# hemera_charger_A.net
KiCad netlist of a schematic drawn in EAGLE
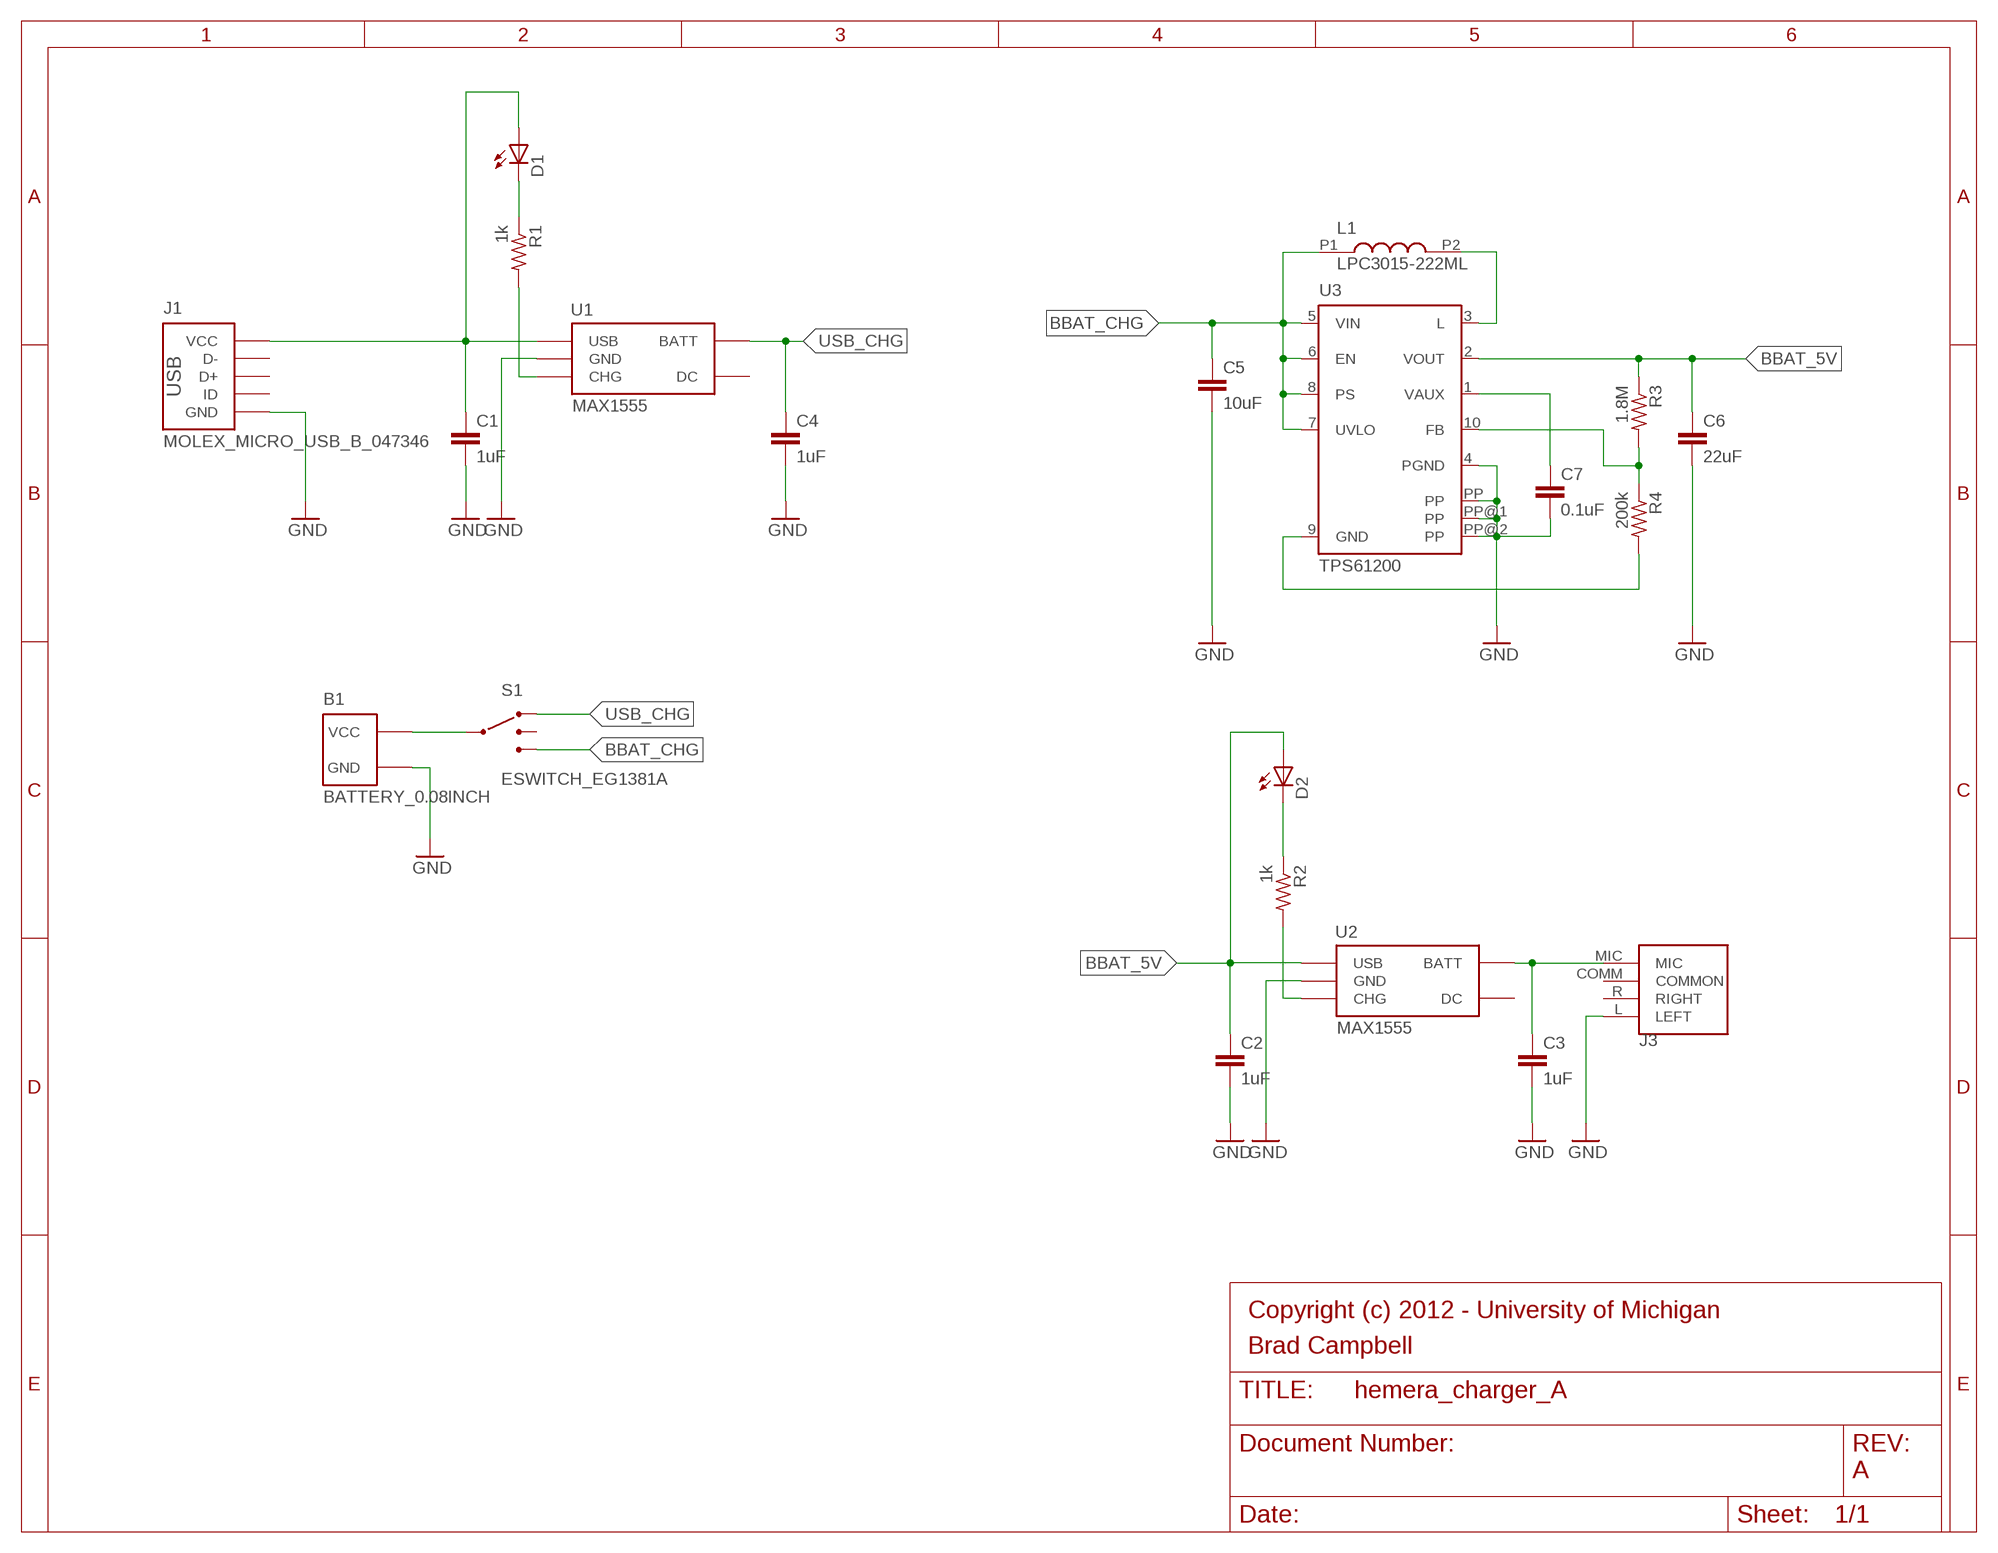
[diagram p0: schematic, sheet 1]

(export (version "E")
  (design (tool "Eeschema 10.0.6"))
  (components
    (comp (ref "B1")
      (value "BATTERY_0.08INCH")
      (footprint "eagle-import:BATTERY_0.08INCH")
      (libsource (lib "eagle-import") (part "BATTERY_0.08INCH"))
    )
    (comp (ref "C1")
      (value "1uF")
      (footprint "eagle-import:C0603")
      (libsource (lib "eagle-import") (part "C-EUC0603"))
    )
    (comp (ref "C2")
      (value "1uF")
      (footprint "eagle-import:C0603")
      (libsource (lib "eagle-import") (part "C-EUC0603"))
    )
    (comp (ref "C3")
      (value "1uF")
      (footprint "eagle-import:C0603")
      (libsource (lib "eagle-import") (part "C-EUC0603"))
    )
    (comp (ref "C4")
      (value "1uF")
      (footprint "eagle-import:C0603")
      (libsource (lib "eagle-import") (part "C-EUC0603"))
    )
    (comp (ref "C5")
      (value "10uF")
      (footprint "eagle-import:C0603")
      (libsource (lib "eagle-import") (part "C-EUC0603"))
    )
    (comp (ref "C6")
      (value "22uF")
      (footprint "eagle-import:C0603")
      (libsource (lib "eagle-import") (part "C-EUC0603"))
    )
    (comp (ref "C7")
      (value "0.1uF")
      (footprint "eagle-import:C0603")
      (libsource (lib "eagle-import") (part "C-EUC0603"))
    )
    (comp (ref "D1")
      (value "LED0603")
      (footprint "eagle-import:LED-0603")
      (libsource (lib "eagle-import") (part "LED0603"))
    )
    (comp (ref "D2")
      (value "LED0603")
      (footprint "eagle-import:LED-0603")
      (libsource (lib "eagle-import") (part "LED0603"))
    )
    (comp (ref "J1")
      (value "MOLEX_MICRO_USB_B_047346")
      (footprint "eagle-import:MOLEX_MICRO_USB_B_047346")
      (libsource (lib "eagle-import") (part "MOLEX_MICRO_USB_B_047346"))
    )
    (comp (ref "J3")
      (value "3.5JACK4CONNSUNSTONE_QUICKTURN")
      (footprint "eagle-import:PLUGBOARDCONNECTOR_SUNSTONE")
      (libsource (lib "eagle-import") (part "3.5JACK4CONNSUNSTONE_QUICKTURN"))
    )
    (comp (ref "L1")
      (value "LPC3015-222ML")
      (footprint "eagle-import:LPS3015")
      (libsource (lib "eagle-import") (part "LPC3015"))
    )
    (comp (ref "R1")
      (value "1k")
      (footprint "eagle-import:R0603")
      (libsource (lib "eagle-import") (part "R-US_R0603"))
    )
    (comp (ref "R2")
      (value "1k")
      (footprint "eagle-import:R0603")
      (libsource (lib "eagle-import") (part "R-US_R0603"))
    )
    (comp (ref "R3")
      (value "1.8M")
      (footprint "eagle-import:R0603")
      (libsource (lib "eagle-import") (part "R-US_R0603"))
    )
    (comp (ref "R4")
      (value "200k")
      (footprint "eagle-import:R0603")
      (libsource (lib "eagle-import") (part "R-US_R0603"))
    )
    (comp (ref "S1")
      (value "ESWITCH_EG1381A")
      (footprint "eagle-import:ESWITCH_EG1381")
      (libsource (lib "eagle-import") (part "ESWITCH_EG1381A"))
    )
    (comp (ref "U1")
      (value "MAX1555")
      (footprint "eagle-import:SOT23-5")
      (libsource (lib "eagle-import") (part "MAX1555"))
    )
    (comp (ref "U2")
      (value "MAX1555")
      (footprint "eagle-import:SOT23-5")
      (libsource (lib "eagle-import") (part "MAX1555"))
    )
    (comp (ref "U3")
      (value "TPS61200")
      (footprint "eagle-import:S-PDSO-N10")
      (fields (field (name "MPN") "TPS61200DRCT"))
      (libsource (lib "eagle-import") (part "TPS61200"))
    )
  )
  (nets
    (net (code "1") (name "/COMMON") (class "Default")
      (node (ref "J3") (pin "COMM") (pinfunction "COMMON_COMM") (pintype "power_in"))
    )
    (net (code "2") (name "BBAT_5V") (class "Default")
      (node (ref "C2") (pin "1") (pinfunction "1_1") (pintype "passive"))
      (node (ref "C6") (pin "1") (pinfunction "1_1") (pintype "passive"))
      (node (ref "D2") (pin "A") (pinfunction "A_A") (pintype "passive"))
      (node (ref "R3") (pin "1") (pinfunction "1_1") (pintype "passive"))
      (node (ref "U2") (pin "1") (pinfunction "USB_1") (pintype "bidirectional"))
      (node (ref "U3") (pin "2") (pinfunction "VOUT_2") (pintype "passive"))
    )
    (net (code "3") (name "BBAT_CHG") (class "Default")
      (node (ref "C5") (pin "1") (pinfunction "1_1") (pintype "passive"))
      (node (ref "L1") (pin "P1") (pinfunction "1_P1") (pintype "input"))
      (node (ref "S1") (pin "4") (pinfunction "4_4") (pintype "bidirectional"))
      (node (ref "U3") (pin "5") (pinfunction "VIN_5") (pintype "input"))
      (node (ref "U3") (pin "6") (pinfunction "EN_6") (pintype "input"))
      (node (ref "U3") (pin "7") (pinfunction "UVLO_7") (pintype "input"))
      (node (ref "U3") (pin "8") (pinfunction "PS_8") (pintype "input"))
    )
    (net (code "4") (name "GND") (class "Default")
      (node (ref "B1") (pin "NEG") (pinfunction "GND_NEG") (pintype "bidirectional"))
      (node (ref "C1") (pin "2") (pinfunction "2_2") (pintype "passive"))
      (node (ref "C2") (pin "2") (pinfunction "2_2") (pintype "passive"))
      (node (ref "C3") (pin "2") (pinfunction "2_2") (pintype "passive"))
      (node (ref "C4") (pin "2") (pinfunction "2_2") (pintype "passive"))
      (node (ref "C5") (pin "2") (pinfunction "2_2") (pintype "passive"))
      (node (ref "C6") (pin "2") (pinfunction "2_2") (pintype "passive"))
      (node (ref "C7") (pin "2") (pinfunction "2_2") (pintype "passive"))
      (node (ref "J1") (pin "GND") (pinfunction "GND_GND") (pintype "bidirectional"))
      (node (ref "J3") (pin "L") (pinfunction "LEFT_L") (pintype "output"))
      (node (ref "U1") (pin "2") (pinfunction "GND_2") (pintype "bidirectional"))
      (node (ref "U2") (pin "2") (pinfunction "GND_2") (pintype "bidirectional"))
      (node (ref "U3") (pin "4") (pinfunction "PGND_4") (pintype "power_in"))
      (node (ref "U3") (pin "PP") (pinfunction "PP_PP") (pintype "power_in"))
      (node (ref "U3") (pin "PP@1") (pinfunction "PP_PP@1") (pintype "power_in"))
      (node (ref "U3") (pin "PP@2") (pinfunction "PP_PP@2") (pintype "power_in"))
    )
    (net (code "5") (name "Net-(B1-VCC)") (class "Default")
      (node (ref "B1") (pin "POS") (pinfunction "VCC_POS") (pintype "bidirectional"))
      (node (ref "S1") (pin "3") (pinfunction "3_3") (pintype "bidirectional"))
    )
    (net (code "6") (name "Net-(D1-PadC)") (class "Default")
      (node (ref "D1") (pin "C") (pinfunction "C_C") (pintype "passive"))
      (node (ref "R1") (pin "1") (pinfunction "1_1") (pintype "passive"))
    )
    (net (code "7") (name "Net-(D2-PadC)") (class "Default")
      (node (ref "D2") (pin "C") (pinfunction "C_C") (pintype "passive"))
      (node (ref "R2") (pin "1") (pinfunction "1_1") (pintype "passive"))
    )
    (net (code "8") (name "Net-(L1-2)") (class "Default")
      (node (ref "L1") (pin "P2") (pinfunction "2_P2") (pintype "output"))
      (node (ref "U3") (pin "3") (pinfunction "L_3") (pintype "input"))
    )
    (net (code "9") (name "Net-(U1-CHG)") (class "Default")
      (node (ref "R1") (pin "2") (pinfunction "2_2") (pintype "passive"))
      (node (ref "U1") (pin "3") (pinfunction "CHG_3") (pintype "bidirectional"))
    )
    (net (code "10") (name "Net-(U1-USB)") (class "Default")
      (node (ref "C1") (pin "1") (pinfunction "1_1") (pintype "passive"))
      (node (ref "D1") (pin "A") (pinfunction "A_A") (pintype "passive"))
      (node (ref "J1") (pin "VCC") (pinfunction "VCC_VCC") (pintype "bidirectional"))
      (node (ref "U1") (pin "1") (pinfunction "USB_1") (pintype "bidirectional"))
    )
    (net (code "11") (name "Net-(U2-BATT)") (class "Default")
      (node (ref "C3") (pin "1") (pinfunction "1_1") (pintype "passive"))
      (node (ref "J3") (pin "MIC") (pinfunction "MIC_MIC") (pintype "input"))
      (node (ref "U2") (pin "5") (pinfunction "BATT_5") (pintype "bidirectional"))
    )
    (net (code "12") (name "Net-(U2-CHG)") (class "Default")
      (node (ref "R2") (pin "2") (pinfunction "2_2") (pintype "passive"))
      (node (ref "U2") (pin "3") (pinfunction "CHG_3") (pintype "bidirectional"))
    )
    (net (code "13") (name "Net-(U3-FB)") (class "Default")
      (node (ref "R3") (pin "2") (pinfunction "2_2") (pintype "passive"))
      (node (ref "R4") (pin "1") (pinfunction "1_1") (pintype "passive"))
      (node (ref "U3") (pin "10") (pinfunction "FB_10") (pintype "input"))
    )
    (net (code "14") (name "Net-(U3-GND)") (class "Default")
      (node (ref "R4") (pin "2") (pinfunction "2_2") (pintype "passive"))
      (node (ref "U3") (pin "9") (pinfunction "GND_9") (pintype "power_in"))
    )
    (net (code "15") (name "Net-(U3-VAUX)") (class "Default")
      (node (ref "C7") (pin "1") (pinfunction "1_1") (pintype "passive"))
      (node (ref "U3") (pin "1") (pinfunction "VAUX_1") (pintype "bidirectional"))
    )
    (net (code "16") (name "USB_CHG") (class "Default")
      (node (ref "C4") (pin "1") (pinfunction "1_1") (pintype "passive"))
      (node (ref "S1") (pin "1") (pinfunction "1_1") (pintype "bidirectional"))
      (node (ref "U1") (pin "5") (pinfunction "BATT_5") (pintype "bidirectional"))
    )
    (net (code "17") (name "unconnected-(J1-PadD+)") (class "Default")
      (node (ref "J1") (pin "D+") (pinfunction "D+_D+") (pintype "bidirectional"))
    )
    (net (code "18") (name "unconnected-(J1-PadD-)") (class "Default")
      (node (ref "J1") (pin "D-") (pinfunction "D-_D-") (pintype "bidirectional"))
    )
    (net (code "19") (name "unconnected-(J1-PadID)") (class "Default")
      (node (ref "J1") (pin "ID") (pinfunction "ID_ID") (pintype "bidirectional"))
    )
    (net (code "20") (name "unconnected-(J3-RIGHT-PadR)") (class "Default")
      (node (ref "J3") (pin "R") (pinfunction "RIGHT_R") (pintype "output"))
    )
    (net (code "21") (name "unconnected-(S1-Pad2)") (class "Default")
      (node (ref "S1") (pin "2") (pinfunction "2_2") (pintype "bidirectional"))
    )
    (net (code "22") (name "unconnected-(U1-DC-Pad4)") (class "Default")
      (node (ref "U1") (pin "4") (pinfunction "DC_4") (pintype "bidirectional"))
    )
    (net (code "23") (name "unconnected-(U2-DC-Pad4)") (class "Default")
      (node (ref "U2") (pin "4") (pinfunction "DC_4") (pintype "bidirectional"))
    )
  )
)
